# NN22_IMU_Adapter01_s00.net
KiCad netlist of a schematic drawn in EAGLE
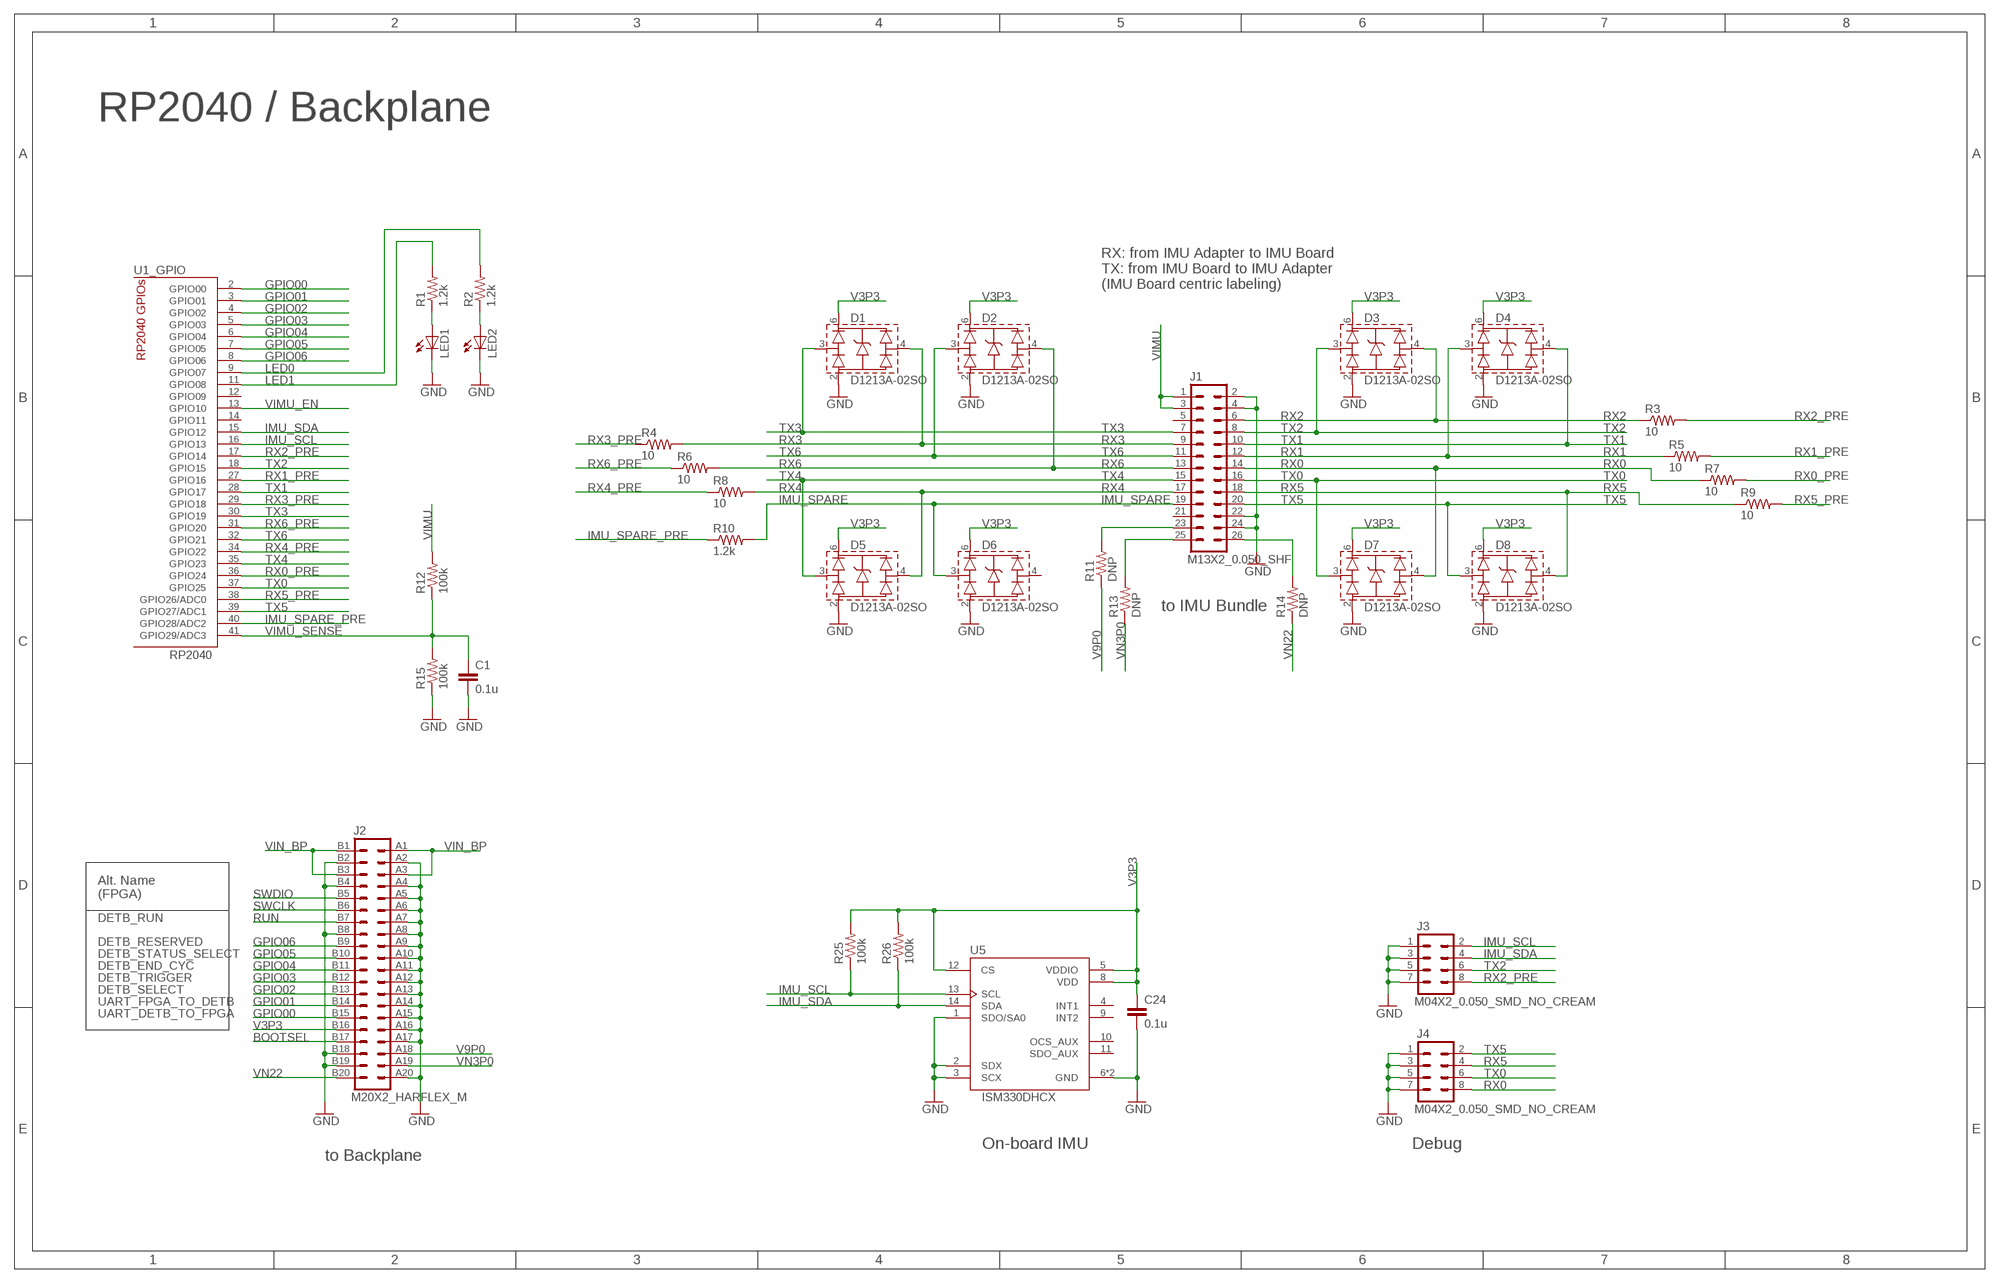
[diagram p0: schematic, sheet 1]
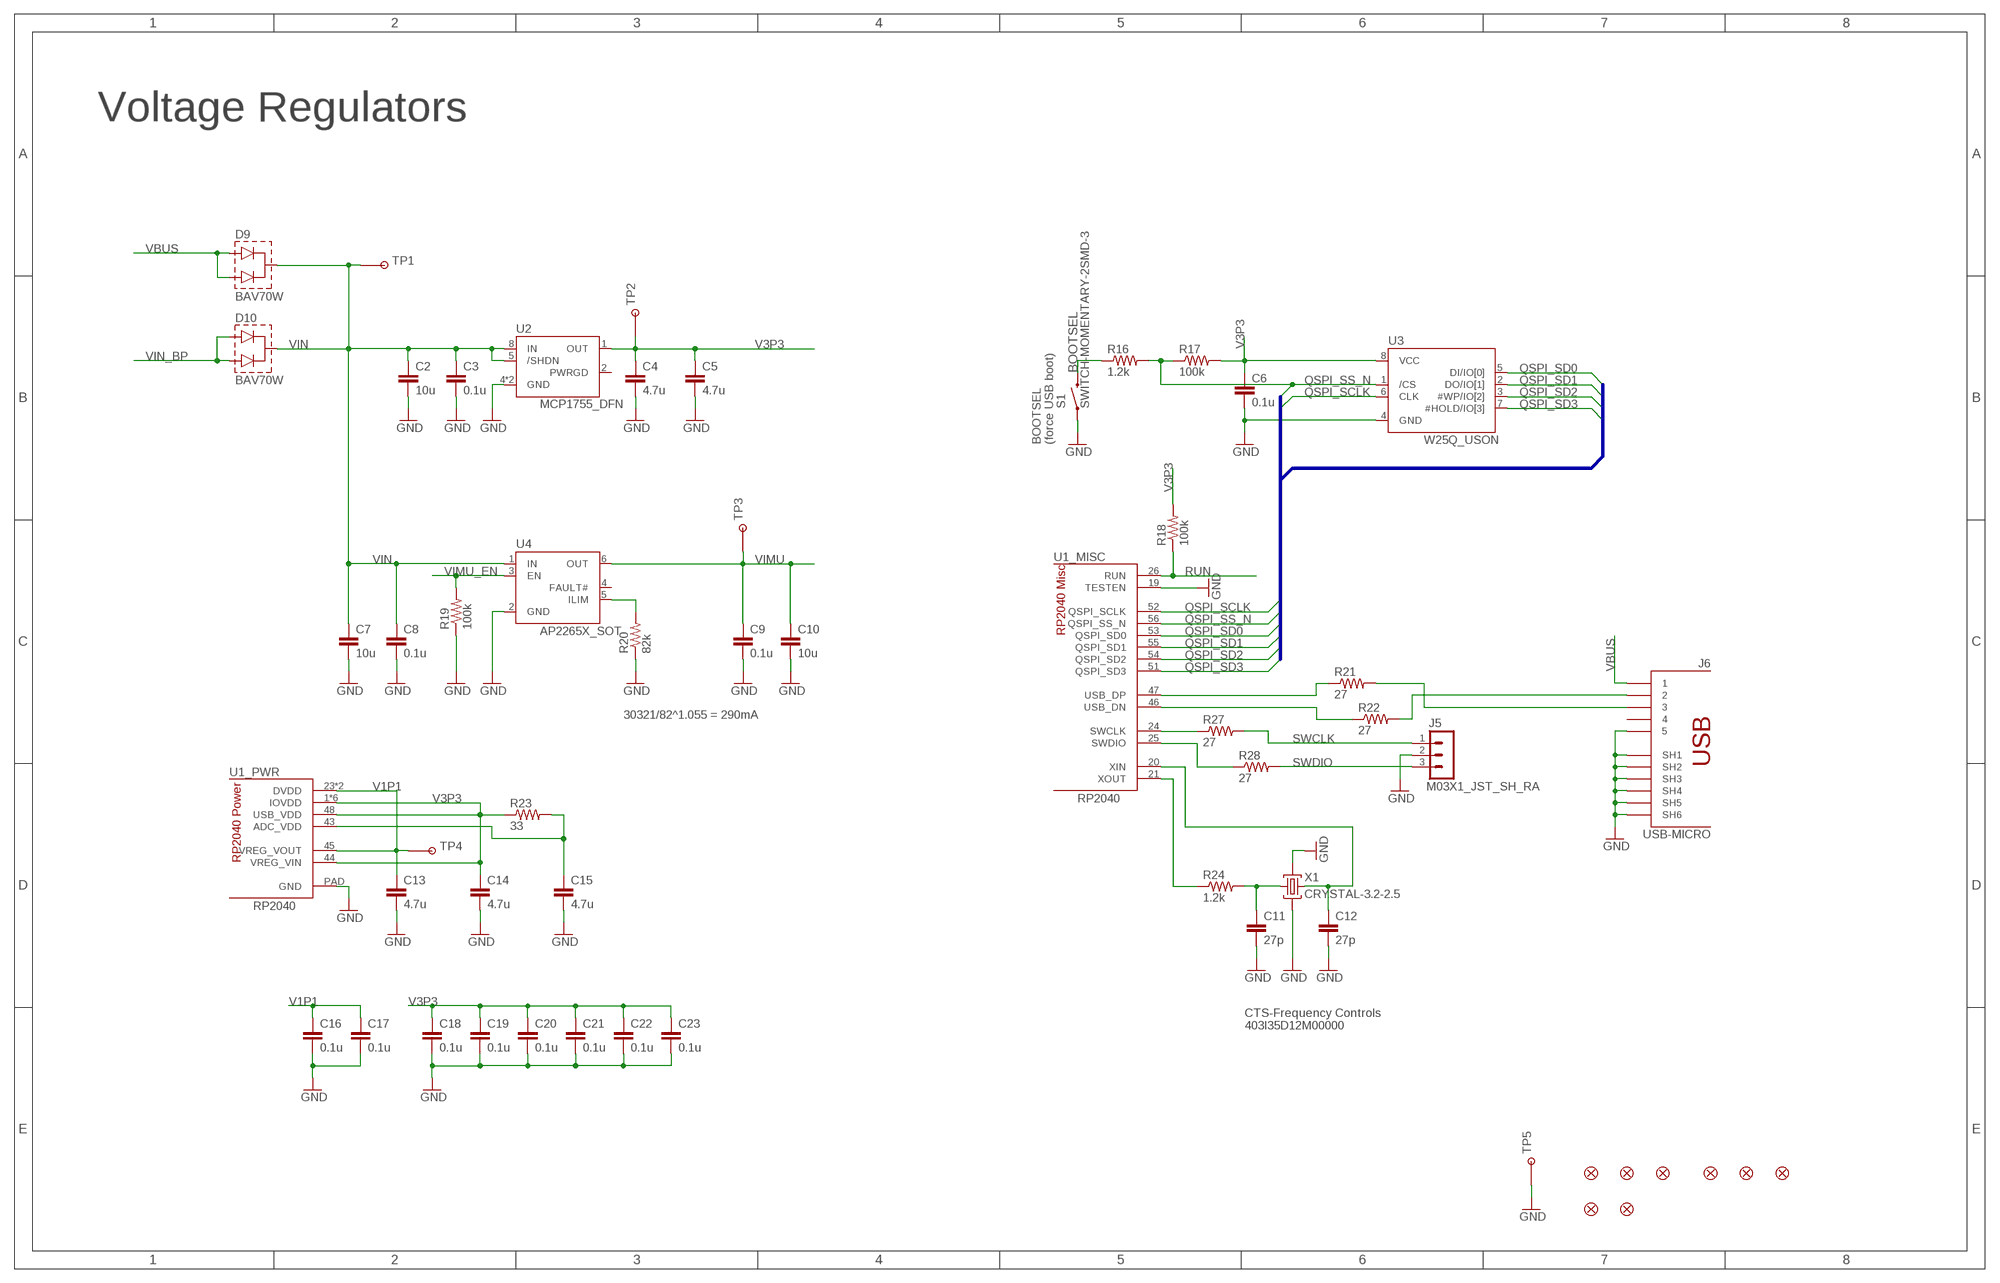
[diagram p1: schematic, sheet 2]

(export (version "E")
  (design (tool "Eeschema 10.0.6"))
  (components
    (comp (ref "C2")
      (value "10u")
      (footprint "eagle-import:0603-CAP")
      (libsource (lib "eagle-import") (part "CAP0603-CAP"))
    )
    (comp (ref "C3")
      (value "0.1u")
      (footprint "eagle-import:0402-CAP")
      (libsource (lib "eagle-import") (part "CAP0402-CAP"))
    )
    (comp (ref "C4")
      (value "4.7u")
      (footprint "eagle-import:0402-CAP")
      (libsource (lib "eagle-import") (part "CAP0402-CAP"))
    )
    (comp (ref "C5")
      (value "4.7u")
      (footprint "eagle-import:0402-CAP")
      (libsource (lib "eagle-import") (part "CAP0402-CAP"))
    )
    (comp (ref "C6")
      (value "0.1u")
      (footprint "eagle-import:0402-CAP")
      (libsource (lib "eagle-import") (part "CAP0402-CAP"))
    )
    (comp (ref "C7")
      (value "10u")
      (footprint "eagle-import:0603-CAP")
      (libsource (lib "eagle-import") (part "CAP0603-CAP"))
    )
    (comp (ref "C8")
      (value "0.1u")
      (footprint "eagle-import:0402-CAP")
      (libsource (lib "eagle-import") (part "CAP0402-CAP"))
    )
    (comp (ref "C9")
      (value "0.1u")
      (footprint "eagle-import:0402-CAP")
      (libsource (lib "eagle-import") (part "CAP0402-CAP"))
    )
    (comp (ref "C10")
      (value "10u")
      (footprint "eagle-import:0603-CAP")
      (libsource (lib "eagle-import") (part "CAP0603-CAP"))
    )
    (comp (ref "C11")
      (value "27p")
      (footprint "eagle-import:0402-CAP")
      (libsource (lib "eagle-import") (part "CAP0402-CAP"))
    )
    (comp (ref "C12")
      (value "27p")
      (footprint "eagle-import:0402-CAP")
      (libsource (lib "eagle-import") (part "CAP0402-CAP"))
    )
    (comp (ref "C13")
      (value "4.7u")
      (footprint "eagle-import:0402-CAP")
      (libsource (lib "eagle-import") (part "CAP0402-CAP"))
    )
    (comp (ref "C14")
      (value "4.7u")
      (footprint "eagle-import:0402-CAP")
      (libsource (lib "eagle-import") (part "CAP0402-CAP"))
    )
    (comp (ref "C15")
      (value "4.7u")
      (footprint "eagle-import:0402-CAP")
      (libsource (lib "eagle-import") (part "CAP0402-CAP"))
    )
    (comp (ref "C16")
      (value "0.1u")
      (footprint "eagle-import:0402-CAP")
      (libsource (lib "eagle-import") (part "CAP0402-CAP"))
    )
    (comp (ref "C17")
      (value "0.1u")
      (footprint "eagle-import:0402-CAP")
      (libsource (lib "eagle-import") (part "CAP0402-CAP"))
    )
    (comp (ref "C18")
      (value "0.1u")
      (footprint "eagle-import:0402-CAP")
      (libsource (lib "eagle-import") (part "CAP0402-CAP"))
    )
    (comp (ref "C19")
      (value "0.1u")
      (footprint "eagle-import:0402-CAP")
      (libsource (lib "eagle-import") (part "CAP0402-CAP"))
    )
    (comp (ref "C20")
      (value "0.1u")
      (footprint "eagle-import:0402-CAP")
      (libsource (lib "eagle-import") (part "CAP0402-CAP"))
    )
    (comp (ref "C21")
      (value "0.1u")
      (footprint "eagle-import:0402-CAP")
      (libsource (lib "eagle-import") (part "CAP0402-CAP"))
    )
    (comp (ref "C22")
      (value "0.1u")
      (footprint "eagle-import:0402-CAP")
      (libsource (lib "eagle-import") (part "CAP0402-CAP"))
    )
    (comp (ref "C23")
      (value "0.1u")
      (footprint "eagle-import:0402-CAP")
      (libsource (lib "eagle-import") (part "CAP0402-CAP"))
    )
    (comp (ref "D9")
      (value "BAV70W")
      (footprint "eagle-import:SOT323")
      (libsource (lib "eagle-import") (part "DIODE-COMMON_CATHODE_SOT323"))
    )
    (comp (ref "D10")
      (value "BAV70W")
      (footprint "eagle-import:SOT323")
      (libsource (lib "eagle-import") (part "DIODE-COMMON_CATHODE_SOT323"))
    )
    (comp (ref "FID1")
      (value "FIDUCIALUFIDUCIAL")
      (footprint "eagle-import:MICRO-FIDUCIAL")
      (libsource (lib "eagle-import") (part "FIDUCIALUFIDUCIAL"))
    )
    (comp (ref "FID2")
      (value "FIDUCIALUFIDUCIAL")
      (footprint "eagle-import:MICRO-FIDUCIAL")
      (libsource (lib "eagle-import") (part "FIDUCIALUFIDUCIAL"))
    )
    (comp (ref "FID3")
      (value "FIDUCIALUFIDUCIAL")
      (footprint "eagle-import:MICRO-FIDUCIAL")
      (libsource (lib "eagle-import") (part "FIDUCIALUFIDUCIAL"))
    )
    (comp (ref "FID4")
      (value "FIDUCIALUFIDUCIAL")
      (footprint "eagle-import:MICRO-FIDUCIAL")
      (libsource (lib "eagle-import") (part "FIDUCIALUFIDUCIAL"))
    )
    (comp (ref "FID5")
      (value "FIDUCIALUFIDUCIAL")
      (footprint "eagle-import:MICRO-FIDUCIAL")
      (libsource (lib "eagle-import") (part "FIDUCIALUFIDUCIAL"))
    )
    (comp (ref "FID6")
      (value "FIDUCIALUFIDUCIAL")
      (footprint "eagle-import:MICRO-FIDUCIAL")
      (libsource (lib "eagle-import") (part "FIDUCIALUFIDUCIAL"))
    )
    (comp (ref "FID7")
      (value "FIDUCIALUFIDUCIAL")
      (footprint "eagle-import:MICRO-FIDUCIAL")
      (libsource (lib "eagle-import") (part "FIDUCIALUFIDUCIAL"))
    )
    (comp (ref "FID8")
      (value "FIDUCIALUFIDUCIAL")
      (footprint "eagle-import:MICRO-FIDUCIAL")
      (libsource (lib "eagle-import") (part "FIDUCIALUFIDUCIAL"))
    )
    (comp (ref "J5")
      (value "M03X1_JST_SH_RA")
      (footprint "eagle-import:M03X1_JST_SH_SM_RA")
      (libsource (lib "eagle-import") (part "M03X1_JST_SH_RA"))
    )
    (comp (ref "J6")
      (value "USB-MICRO")
      (footprint "eagle-import:USB-MICRO")
      (libsource (lib "eagle-import") (part "USB-MICRO"))
    )
    (comp (ref "R16")
      (value "1.2k")
      (footprint "eagle-import:0402-RES")
      (libsource (lib "eagle-import") (part "RESISTOR0402-RES"))
    )
    (comp (ref "R17")
      (value "100k")
      (footprint "eagle-import:0402-RES")
      (libsource (lib "eagle-import") (part "RESISTOR0402-RES"))
    )
    (comp (ref "R18")
      (value "100k")
      (footprint "eagle-import:0402-RES")
      (libsource (lib "eagle-import") (part "RESISTOR0402-RES"))
    )
    (comp (ref "R19")
      (value "100k")
      (footprint "eagle-import:0402-RES")
      (libsource (lib "eagle-import") (part "RESISTOR0402-RES"))
    )
    (comp (ref "R20")
      (value "82k")
      (footprint "eagle-import:0402-RES")
      (libsource (lib "eagle-import") (part "RESISTOR0402-RES"))
    )
    (comp (ref "R21")
      (value "27")
      (footprint "eagle-import:0402-RES")
      (libsource (lib "eagle-import") (part "RESISTOR0402-RES"))
    )
    (comp (ref "R22")
      (value "27")
      (footprint "eagle-import:0402-RES")
      (libsource (lib "eagle-import") (part "RESISTOR0402-RES"))
    )
    (comp (ref "R23")
      (value "33")
      (footprint "eagle-import:0402-RES")
      (libsource (lib "eagle-import") (part "RESISTOR0402-RES"))
    )
    (comp (ref "R24")
      (value "1.2k")
      (footprint "eagle-import:0402-RES")
      (libsource (lib "eagle-import") (part "RESISTOR0402-RES"))
    )
    (comp (ref "R27")
      (value "27")
      (footprint "eagle-import:0402-RES")
      (libsource (lib "eagle-import") (part "RESISTOR0402-RES"))
    )
    (comp (ref "R28")
      (value "27")
      (footprint "eagle-import:0402-RES")
      (libsource (lib "eagle-import") (part "RESISTOR0402-RES"))
    )
    (comp (ref "S1")
      (value "SWITCH-MOMENTARY-2SMD-3")
      (footprint "eagle-import:TACTILE_SWITCH_SMD-3")
      (libsource (lib "eagle-import") (part "SWITCH-MOMENTARY-2SMD-3"))
    )
    (comp (ref "TP1")
      (value "TESTPOINT_ROUND")
      (footprint "eagle-import:TESTPAD_ROUND")
      (libsource (lib "eagle-import") (part "TESTPOINT_ROUND"))
    )
    (comp (ref "TP2")
      (value "TESTPOINT_ROUND")
      (footprint "eagle-import:TESTPAD_ROUND")
      (libsource (lib "eagle-import") (part "TESTPOINT_ROUND"))
    )
    (comp (ref "TP3")
      (value "TESTPOINT_ROUND")
      (footprint "eagle-import:TESTPAD_ROUND")
      (libsource (lib "eagle-import") (part "TESTPOINT_ROUND"))
    )
    (comp (ref "TP4")
      (value "TESTPOINTPADSMALL")
      (footprint "eagle-import:TESTPAD_SMALL")
      (libsource (lib "eagle-import") (part "TESTPOINTPADSMALL"))
    )
    (comp (ref "TP5")
      (value "TESTPOINT1X01")
      (footprint "eagle-import:1X01")
      (libsource (lib "eagle-import") (part "TESTPOINT1X01"))
    )
    (comp (ref "U1")
      (value "RP2040")
      (footprint "eagle-import:QFN-56_EP")
      (libsource (lib "eagle-import") (part "RP2040"))
    )
    (comp (ref "U2")
      (value "MCP1755_DFN")
      (footprint "eagle-import:DFN8_2X3MM")
      (libsource (lib "eagle-import") (part "MCP1755_DFN"))
    )
    (comp (ref "U3")
      (value "W25Q_USON")
      (footprint "eagle-import:USON8L-2X3MM")
      (libsource (lib "eagle-import") (part "W25Q_USON"))
    )
    (comp (ref "U4")
      (value "AP2265X_SOT")
      (footprint "eagle-import:SOT23-6")
      (libsource (lib "eagle-import") (part "AP2265X_SOT"))
    )
    (comp (ref "X1")
      (value "CRYSTAL-3.2-2.5")
      (footprint "eagle-import:CRYSTAL-3.2-2.5")
      (libsource (lib "eagle-import") (part "CRYSTAL-3.2-2.5"))
    )
    (comp (ref "C1")
      (value "0.1u")
      (footprint "eagle-import:0402-CAP")
      (libsource (lib "eagle-import") (part "CAP0402-CAP"))
    )
    (comp (ref "C24")
      (value "0.1u")
      (footprint "eagle-import:0402-CAP")
      (libsource (lib "eagle-import") (part "CAP0402-CAP"))
    )
    (comp (ref "D1")
      (value "D1213A-02SO")
      (footprint "eagle-import:SOT23-6")
      (libsource (lib "eagle-import") (part "D1213A-02SO"))
    )
    (comp (ref "D2")
      (value "D1213A-02SO")
      (footprint "eagle-import:SOT23-6")
      (libsource (lib "eagle-import") (part "D1213A-02SO"))
    )
    (comp (ref "D3")
      (value "D1213A-02SO")
      (footprint "eagle-import:SOT23-6")
      (libsource (lib "eagle-import") (part "D1213A-02SO"))
    )
    (comp (ref "D4")
      (value "D1213A-02SO")
      (footprint "eagle-import:SOT23-6")
      (libsource (lib "eagle-import") (part "D1213A-02SO"))
    )
    (comp (ref "D5")
      (value "D1213A-02SO")
      (footprint "eagle-import:SOT23-6")
      (libsource (lib "eagle-import") (part "D1213A-02SO"))
    )
    (comp (ref "D6")
      (value "D1213A-02SO")
      (footprint "eagle-import:SOT23-6")
      (libsource (lib "eagle-import") (part "D1213A-02SO"))
    )
    (comp (ref "D7")
      (value "D1213A-02SO")
      (footprint "eagle-import:SOT23-6")
      (libsource (lib "eagle-import") (part "D1213A-02SO"))
    )
    (comp (ref "D8")
      (value "D1213A-02SO")
      (footprint "eagle-import:SOT23-6")
      (libsource (lib "eagle-import") (part "D1213A-02SO"))
    )
    (comp (ref "J1")
      (value "M13X2_0.050_SHF")
      (footprint "eagle-import:M13X2_0.050_SHF")
      (libsource (lib "eagle-import") (part "M13X2_0.050_SHF"))
    )
    (comp (ref "J2")
      (value "M20X2_HARFLEX_M")
      (footprint "eagle-import:M20X2_HARFLEX_M")
      (libsource (lib "eagle-import") (part "M20X2_HARFLEX_M"))
    )
    (comp (ref "J3")
      (value "M04X2_0.050_SMD_NO_CREAM")
      (footprint "eagle-import:M04X2_0.050_SMD_NO_CREAM")
      (libsource (lib "eagle-import") (part "M04X2_0.050_SMD_NO_CREAM"))
    )
    (comp (ref "J4")
      (value "M04X2_0.050_SMD_NO_CREAM")
      (footprint "eagle-import:M04X2_0.050_SMD_NO_CREAM")
      (libsource (lib "eagle-import") (part "M04X2_0.050_SMD_NO_CREAM"))
    )
    (comp (ref "LED1")
      (value "LED0603")
      (footprint "eagle-import:LED-0603")
      (libsource (lib "eagle-import") (part "LED0603"))
    )
    (comp (ref "LED2")
      (value "LED0603")
      (footprint "eagle-import:LED-0603")
      (libsource (lib "eagle-import") (part "LED0603"))
    )
    (comp (ref "R1")
      (value "1.2k")
      (footprint "eagle-import:0402-RES")
      (libsource (lib "eagle-import") (part "RESISTOR0402-RES"))
    )
    (comp (ref "R2")
      (value "1.2k")
      (footprint "eagle-import:0402-RES")
      (libsource (lib "eagle-import") (part "RESISTOR0402-RES"))
    )
    (comp (ref "R3")
      (value "10")
      (footprint "eagle-import:0402-RES")
      (libsource (lib "eagle-import") (part "RESISTOR0402-RES"))
    )
    (comp (ref "R4")
      (value "10")
      (footprint "eagle-import:0402-RES")
      (libsource (lib "eagle-import") (part "RESISTOR0402-RES"))
    )
    (comp (ref "R5")
      (value "10")
      (footprint "eagle-import:0402-RES")
      (libsource (lib "eagle-import") (part "RESISTOR0402-RES"))
    )
    (comp (ref "R6")
      (value "10")
      (footprint "eagle-import:0402-RES")
      (libsource (lib "eagle-import") (part "RESISTOR0402-RES"))
    )
    (comp (ref "R7")
      (value "10")
      (footprint "eagle-import:0402-RES")
      (libsource (lib "eagle-import") (part "RESISTOR0402-RES"))
    )
    (comp (ref "R8")
      (value "10")
      (footprint "eagle-import:0402-RES")
      (libsource (lib "eagle-import") (part "RESISTOR0402-RES"))
    )
    (comp (ref "R9")
      (value "10")
      (footprint "eagle-import:0402-RES")
      (libsource (lib "eagle-import") (part "RESISTOR0402-RES"))
    )
    (comp (ref "R10")
      (value "1.2k")
      (footprint "eagle-import:0402-RES")
      (libsource (lib "eagle-import") (part "RESISTOR0402-RES"))
    )
    (comp (ref "R11")
      (value "DNP")
      (footprint "eagle-import:0603-RES")
      (libsource (lib "eagle-import") (part "RESISTOR0603-RES"))
    )
    (comp (ref "R12")
      (value "100k")
      (footprint "eagle-import:0402-RES")
      (libsource (lib "eagle-import") (part "RESISTOR0402-RES"))
    )
    (comp (ref "R13")
      (value "DNP")
      (footprint "eagle-import:0603-RES")
      (libsource (lib "eagle-import") (part "RESISTOR0603-RES"))
    )
    (comp (ref "R14")
      (value "DNP")
      (footprint "eagle-import:0603-RES")
      (libsource (lib "eagle-import") (part "RESISTOR0603-RES"))
    )
    (comp (ref "R15")
      (value "100k")
      (footprint "eagle-import:0402-RES")
      (libsource (lib "eagle-import") (part "RESISTOR0402-RES"))
    )
    (comp (ref "R25")
      (value "100k")
      (footprint "eagle-import:0402-RES")
      (libsource (lib "eagle-import") (part "RESISTOR0402-RES"))
    )
    (comp (ref "R26")
      (value "100k")
      (footprint "eagle-import:0402-RES")
      (libsource (lib "eagle-import") (part "RESISTOR0402-RES"))
    )
    (comp (ref "U5")
      (value "ISM330DHCX")
      (footprint "eagle-import:LGA14-L")
      (fields (field (name "MF") "STMicroelectronics"))
      (libsource (lib "eagle-import") (part "ISM330DHCX"))
    )
  )
  (nets
    (net (code "1") (name "BOOTSEL") (class "Default")
      (node (ref "J2") (pin "B17") (pinfunction "33_B17") (pintype "passive"))
      (node (ref "R16") (pin "1") (pinfunction "1_1") (pintype "passive"))
      (node (ref "S1") (pin "4") (pinfunction "2_4") (pintype "passive"))
    )
    (net (code "2") (name "GND") (class "Default")
      (node (ref "C1") (pin "2") (pinfunction "2_2") (pintype "passive"))
      (node (ref "C10") (pin "2") (pinfunction "2_2") (pintype "passive"))
      (node (ref "C11") (pin "2") (pinfunction "2_2") (pintype "passive"))
      (node (ref "C12") (pin "2") (pinfunction "2_2") (pintype "passive"))
      (node (ref "C13") (pin "2") (pinfunction "2_2") (pintype "passive"))
      (node (ref "C14") (pin "2") (pinfunction "2_2") (pintype "passive"))
      (node (ref "C15") (pin "2") (pinfunction "2_2") (pintype "passive"))
      (node (ref "C16") (pin "2") (pinfunction "2_2") (pintype "passive"))
      (node (ref "C17") (pin "2") (pinfunction "2_2") (pintype "passive"))
      (node (ref "C18") (pin "2") (pinfunction "2_2") (pintype "passive"))
      (node (ref "C19") (pin "2") (pinfunction "2_2") (pintype "passive"))
      (node (ref "C2") (pin "2") (pinfunction "2_2") (pintype "passive"))
      (node (ref "C20") (pin "2") (pinfunction "2_2") (pintype "passive"))
      (node (ref "C21") (pin "2") (pinfunction "2_2") (pintype "passive"))
      (node (ref "C22") (pin "2") (pinfunction "2_2") (pintype "passive"))
      (node (ref "C23") (pin "2") (pinfunction "2_2") (pintype "passive"))
      (node (ref "C24") (pin "2") (pinfunction "2_2") (pintype "passive"))
      (node (ref "C3") (pin "2") (pinfunction "2_2") (pintype "passive"))
      (node (ref "C4") (pin "2") (pinfunction "2_2") (pintype "passive"))
      (node (ref "C5") (pin "2") (pinfunction "2_2") (pintype "passive"))
      (node (ref "C6") (pin "2") (pinfunction "2_2") (pintype "passive"))
      (node (ref "C7") (pin "2") (pinfunction "2_2") (pintype "passive"))
      (node (ref "C8") (pin "2") (pinfunction "2_2") (pintype "passive"))
      (node (ref "C9") (pin "2") (pinfunction "2_2") (pintype "passive"))
      (node (ref "D1") (pin "2") (pinfunction "VN_2") (pintype "power_in"))
      (node (ref "D2") (pin "2") (pinfunction "VN_2") (pintype "power_in"))
      (node (ref "D3") (pin "2") (pinfunction "VN_2") (pintype "power_in"))
      (node (ref "D4") (pin "2") (pinfunction "VN_2") (pintype "power_in"))
      (node (ref "D5") (pin "2") (pinfunction "VN_2") (pintype "power_in"))
      (node (ref "D6") (pin "2") (pinfunction "VN_2") (pintype "power_in"))
      (node (ref "D7") (pin "2") (pinfunction "VN_2") (pintype "power_in"))
      (node (ref "D8") (pin "2") (pinfunction "VN_2") (pintype "power_in"))
      (node (ref "J1") (pin "2") (pinfunction "2_2") (pintype "passive"))
      (node (ref "J1") (pin "22") (pinfunction "22_22") (pintype "passive"))
      (node (ref "J1") (pin "24") (pinfunction "24_24") (pintype "passive"))
      (node (ref "J1") (pin "4") (pinfunction "4_4") (pintype "passive"))
      (node (ref "J2") (pin "A10") (pinfunction "20_A10") (pintype "passive"))
      (node (ref "J2") (pin "A11") (pinfunction "22_A11") (pintype "passive"))
      (node (ref "J2") (pin "A12") (pinfunction "24_A12") (pintype "passive"))
      (node (ref "J2") (pin "A13") (pinfunction "26_A13") (pintype "passive"))
      (node (ref "J2") (pin "A14") (pinfunction "28_A14") (pintype "passive"))
      (node (ref "J2") (pin "A15") (pinfunction "30_A15") (pintype "passive"))
      (node (ref "J2") (pin "A16") (pinfunction "32_A16") (pintype "passive"))
      (node (ref "J2") (pin "A17") (pinfunction "34_A17") (pintype "passive"))
      (node (ref "J2") (pin "A2") (pinfunction "4_A2") (pintype "passive"))
      (node (ref "J2") (pin "A20") (pinfunction "40_A20") (pintype "passive"))
      (node (ref "J2") (pin "A4") (pinfunction "8_A4") (pintype "passive"))
      (node (ref "J2") (pin "A5") (pinfunction "10_A5") (pintype "passive"))
      (node (ref "J2") (pin "A6") (pinfunction "12_A6") (pintype "passive"))
      (node (ref "J2") (pin "A7") (pinfunction "14_A7") (pintype "passive"))
      (node (ref "J2") (pin "A8") (pinfunction "16_A8") (pintype "passive"))
      (node (ref "J2") (pin "A9") (pinfunction "18_A9") (pintype "passive"))
      (node (ref "J2") (pin "B18") (pinfunction "35_B18") (pintype "passive"))
      (node (ref "J2") (pin "B19") (pinfunction "37_B19") (pintype "passive"))
      (node (ref "J2") (pin "B2") (pinfunction "3_B2") (pintype "passive"))
      (node (ref "J2") (pin "B4") (pinfunction "7_B4") (pintype "passive"))
      (node (ref "J2") (pin "B8") (pinfunction "15_B8") (pintype "passive"))
      (node (ref "J3") (pin "1") (pinfunction "1_1") (pintype "passive"))
      (node (ref "J3") (pin "3") (pinfunction "3_3") (pintype "passive"))
      (node (ref "J3") (pin "5") (pinfunction "5_5") (pintype "passive"))
      (node (ref "J3") (pin "7") (pinfunction "7_7") (pintype "passive"))
      (node (ref "J4") (pin "1") (pinfunction "1_1") (pintype "passive"))
      (node (ref "J4") (pin "3") (pinfunction "3_3") (pintype "passive"))
      (node (ref "J4") (pin "5") (pinfunction "5_5") (pintype "passive"))
      (node (ref "J4") (pin "7") (pinfunction "7_7") (pintype "passive"))
      (node (ref "J5") (pin "2") (pinfunction "2_2") (pintype "passive"))
      (node (ref "J6") (pin "5") (pinfunction "5_5") (pintype "bidirectional"))
      (node (ref "J6") (pin "SH1") (pinfunction "SH1_SH1") (pintype "bidirectional"))
      (node (ref "J6") (pin "SH2") (pinfunction "SH2_SH2") (pintype "bidirectional"))
      (node (ref "J6") (pin "SH3") (pinfunction "SH3_SH3") (pintype "bidirectional"))
      (node (ref "J6") (pin "SH4") (pinfunction "SH4_SH4") (pintype "bidirectional"))
      (node (ref "J6") (pin "SH5") (pinfunction "SH5_SH5") (pintype "bidirectional"))
      (node (ref "J6") (pin "SH6") (pinfunction "SH6_SH6") (pintype "bidirectional"))
      (node (ref "LED1") (pin "C") (pinfunction "C_C") (pintype "passive"))
      (node (ref "LED2") (pin "C") (pinfunction "C_C") (pintype "passive"))
      (node (ref "R15") (pin "1") (pinfunction "1_1") (pintype "passive"))
      (node (ref "R19") (pin "1") (pinfunction "1_1") (pintype "passive"))
      (node (ref "R20") (pin "1") (pinfunction "1_1") (pintype "passive"))
      (node (ref "S1") (pin "1") (pinfunction "1_1") (pintype "passive"))
      (node (ref "TP5") (pin "1") (pinfunction "P$1_1") (pintype "bidirectional"))
      (node (ref "U1") (pin "19") (pinfunction "TESTEN_19") (pintype "input"))
      (node (ref "U1") (pin "PAD") (pinfunction "GND_PAD") (pintype "power_in"))
      (node (ref "U2") (pin "4") (pinfunction "GND_4") (pintype "power_in"))
      (node (ref "U2") (pin "P") (pinfunction "GND_P") (pintype "power_in"))
      (node (ref "U3") (pin "4") (pinfunction "GND_4") (pintype "power_in"))
      (node (ref "U4") (pin "2") (pinfunction "GND_2") (pintype "power_in"))
      (node (ref "U5") (pin "1") (pinfunction "SDO/SA0_1") (pintype "bidirectional"))
      (node (ref "U5") (pin "2") (pinfunction "SDX_2") (pintype "bidirectional"))
      (node (ref "U5") (pin "3") (pinfunction "SCX_3") (pintype "bidirectional"))
      (node (ref "U5") (pin "6") (pinfunction "GND_6") (pintype "power_in"))
      (node (ref "U5") (pin "7") (pinfunction "GND_7") (pintype "power_in"))
      (node (ref "X1") (pin "2") (pinfunction "GND_2") (pintype "passive"))
      (node (ref "X1") (pin "4") (pinfunction "GND_4") (pintype "passive"))
    )
    (net (code "3") (name "GPIO00") (class "Default")
      (node (ref "J2") (pin "B15") (pinfunction "29_B15") (pintype "passive"))
      (node (ref "U1") (pin "2") (pinfunction "GPIO00_2") (pintype "bidirectional"))
    )
    (net (code "4") (name "GPIO01") (class "Default")
      (node (ref "J2") (pin "B14") (pinfunction "27_B14") (pintype "passive"))
      (node (ref "U1") (pin "3") (pinfunction "GPIO01_3") (pintype "bidirectional"))
    )
    (net (code "5") (name "GPIO02") (class "Default")
      (node (ref "J2") (pin "B13") (pinfunction "25_B13") (pintype "passive"))
      (node (ref "U1") (pin "4") (pinfunction "GPIO02_4") (pintype "bidirectional"))
    )
    (net (code "6") (name "GPIO03") (class "Default")
      (node (ref "J2") (pin "B12") (pinfunction "23_B12") (pintype "passive"))
      (node (ref "U1") (pin "5") (pinfunction "GPIO03_5") (pintype "bidirectional"))
    )
    (net (code "7") (name "GPIO04") (class "Default")
      (node (ref "J2") (pin "B11") (pinfunction "21_B11") (pintype "passive"))
      (node (ref "U1") (pin "6") (pinfunction "GPIO04_6") (pintype "bidirectional"))
    )
    (net (code "8") (name "GPIO05") (class "Default")
      (node (ref "J2") (pin "B10") (pinfunction "19_B10") (pintype "passive"))
      (node (ref "U1") (pin "7") (pinfunction "GPIO05_7") (pintype "bidirectional"))
    )
    (net (code "9") (name "GPIO06") (class "Default")
      (node (ref "J2") (pin "B9") (pinfunction "17_B9") (pintype "passive"))
      (node (ref "U1") (pin "8") (pinfunction "GPIO06_8") (pintype "bidirectional"))
    )
    (net (code "10") (name "IMU_SCL") (class "Default")
      (node (ref "J3") (pin "2") (pinfunction "2_2") (pintype "passive"))
      (node (ref "R25") (pin "1") (pinfunction "1_1") (pintype "passive"))
      (node (ref "U1") (pin "16") (pinfunction "GPIO13_16") (pintype "bidirectional"))
      (node (ref "U5") (pin "13") (pinfunction "SCL_13") (pintype "input"))
    )
    (net (code "11") (name "IMU_SDA") (class "Default")
      (node (ref "J3") (pin "4") (pinfunction "4_4") (pintype "passive"))
      (node (ref "R26") (pin "1") (pinfunction "1_1") (pintype "passive"))
      (node (ref "U1") (pin "15") (pinfunction "GPIO12_15") (pintype "bidirectional"))
      (node (ref "U5") (pin "14") (pinfunction "SDA_14") (pintype "bidirectional"))
    )
    (net (code "12") (name "IMU_SPARE") (class "Default")
      (node (ref "D6") (pin "3") (pinfunction "CH1_3") (pintype "bidirectional"))
      (node (ref "J1") (pin "19") (pinfunction "19_19") (pintype "passive"))
      (node (ref "R10") (pin "2") (pinfunction "2_2") (pintype "passive"))
    )
    (net (code "13") (name "IMU_SPARE_PRE") (class "Default")
      (node (ref "R10") (pin "1") (pinfunction "1_1") (pintype "passive"))
      (node (ref "U1") (pin "40") (pinfunction "GPIO28/ADC2_40") (pintype "bidirectional"))
    )
    (net (code "14") (name "LED0") (class "Default")
      (node (ref "R2") (pin "2") (pinfunction "2_2") (pintype "passive"))
      (node (ref "U1") (pin "9") (pinfunction "GPIO07_9") (pintype "bidirectional"))
    )
    (net (code "15") (name "LED1") (class "Default")
      (node (ref "R1") (pin "2") (pinfunction "2_2") (pintype "passive"))
      (node (ref "U1") (pin "11") (pinfunction "GPIO08_11") (pintype "bidirectional"))
    )
    (net (code "16") (name "Net-(J1-Pad23)") (class "Default")
      (node (ref "J1") (pin "23") (pinfunction "23_23") (pintype "passive"))
      (node (ref "R11") (pin "2") (pinfunction "2_2") (pintype "passive"))
    )
    (net (code "17") (name "Net-(J1-Pad25)") (class "Default")
      (node (ref "J1") (pin "25") (pinfunction "25_25") (pintype "passive"))
      (node (ref "R13") (pin "2") (pinfunction "2_2") (pintype "passive"))
    )
    (net (code "18") (name "Net-(J1-Pad26)") (class "Default")
      (node (ref "J1") (pin "26") (pinfunction "26_26") (pintype "passive"))
      (node (ref "R14") (pin "2") (pinfunction "2_2") (pintype "passive"))
    )
    (net (code "19") (name "Net-(J6-Pad2)") (class "Default")
      (node (ref "J6") (pin "2") (pinfunction "2_2") (pintype "bidirectional"))
      (node (ref "R22") (pin "2") (pinfunction "2_2") (pintype "passive"))
    )
    (net (code "20") (name "Net-(J6-Pad3)") (class "Default")
      (node (ref "J6") (pin "3") (pinfunction "3_3") (pintype "bidirectional"))
      (node (ref "R21") (pin "2") (pinfunction "2_2") (pintype "passive"))
    )
    (net (code "21") (name "Net-(LED1-PadA)") (class "Default")
      (node (ref "LED1") (pin "A") (pinfunction "A_A") (pintype "passive"))
      (node (ref "R1") (pin "1") (pinfunction "1_1") (pintype "passive"))
    )
    (net (code "22") (name "Net-(LED2-PadA)") (class "Default")
      (node (ref "LED2") (pin "A") (pinfunction "A_A") (pintype "passive"))
      (node (ref "R2") (pin "1") (pinfunction "1_1") (pintype "passive"))
    )
    (net (code "23") (name "Net-(U1B-SWCLK)") (class "Default")
      (node (ref "R27") (pin "1") (pinfunction "1_1") (pintype "passive"))
      (node (ref "U1") (pin "24") (pinfunction "SWCLK_24") (pintype "input"))
    )
    (net (code "24") (name "Net-(U1B-SWDIO)") (class "Default")
      (node (ref "R28") (pin "1") (pinfunction "1_1") (pintype "passive"))
      (node (ref "U1") (pin "25") (pinfunction "SWDIO_25") (pintype "bidirectional"))
    )
    (net (code "25") (name "Net-(U1B-USB_DN)") (class "Default")
      (node (ref "R22") (pin "1") (pinfunction "1_1") (pintype "passive"))
      (node (ref "U1") (pin "46") (pinfunction "USB_DN_46") (pintype "bidirectional"))
    )
    (net (code "26") (name "Net-(U1B-USB_DP)") (class "Default")
      (node (ref "R21") (pin "1") (pinfunction "1_1") (pintype "passive"))
      (node (ref "U1") (pin "47") (pinfunction "USB_DP_47") (pintype "bidirectional"))
    )
    (net (code "27") (name "Net-(U1B-XIN)") (class "Default")
      (node (ref "C12") (pin "1") (pinfunction "1_1") (pintype "passive"))
      (node (ref "U1") (pin "20") (pinfunction "XIN_20") (pintype "bidirectional"))
      (node (ref "X1") (pin "3") (pinfunction "C2_3") (pintype "passive"))
    )
    (net (code "28") (name "Net-(U1B-XOUT)") (class "Default")
      (node (ref "R24") (pin "1") (pinfunction "1_1") (pintype "passive"))
      (node (ref "U1") (pin "21") (pinfunction "XOUT_21") (pintype "bidirectional"))
    )
    (net (code "29") (name "Net-(U1C-ADC_VDD)") (class "Default")
      (node (ref "C15") (pin "1") (pinfunction "1_1") (pintype "passive"))
      (node (ref "R23") (pin "2") (pinfunction "2_2") (pintype "passive"))
      (node (ref "U1") (pin "43") (pinfunction "ADC_VDD_43") (pintype "power_in"))
    )
    (net (code "30") (name "Net-(U4-ILIM)") (class "Default")
      (node (ref "R20") (pin "2") (pinfunction "2_2") (pintype "passive"))
      (node (ref "U4") (pin "5") (pinfunction "ILIM_5") (pintype "bidirectional"))
    )
    (net (code "31") (name "Net-(X1-C1)") (class "Default")
      (node (ref "C11") (pin "1") (pinfunction "1_1") (pintype "passive"))
      (node (ref "R24") (pin "2") (pinfunction "2_2") (pintype "passive"))
      (node (ref "X1") (pin "1") (pinfunction "C1_1") (pintype "passive"))
    )
    (net (code "32") (name "QSPI_SCLK") (class "Default")
      (node (ref "U1") (pin "52") (pinfunction "QSPI_SCLK_52") (pintype "output"))
      (node (ref "U3") (pin "6") (pinfunction "CLK_6") (pintype "input"))
    )
    (net (code "33") (name "QSPI_SD0") (class "Default")
      (node (ref "U1") (pin "53") (pinfunction "QSPI_SD0_53") (pintype "bidirectional"))
      (node (ref "U3") (pin "5") (pinfunction "DI/IO[0]_5") (pintype "bidirectional"))
    )
    (net (code "34") (name "QSPI_SD1") (class "Default")
      (node (ref "U1") (pin "55") (pinfunction "QSPI_SD1_55") (pintype "bidirectional"))
      (node (ref "U3") (pin "2") (pinfunction "DO/IO[1]_2") (pintype "bidirectional"))
    )
    (net (code "35") (name "QSPI_SD2") (class "Default")
      (node (ref "U1") (pin "54") (pinfunction "QSPI_SD2_54") (pintype "bidirectional"))
      (node (ref "U3") (pin "3") (pinfunction "#WP/IO[2]_3") (pintype "bidirectional"))
    )
    (net (code "36") (name "QSPI_SD3") (class "Default")
      (node (ref "U1") (pin "51") (pinfunction "QSPI_SD3_51") (pintype "bidirectional"))
      (node (ref "U3") (pin "7") (pinfunction "#HOLD/IO[3]_7") (pintype "bidirectional"))
    )
    (net (code "37") (name "QSPI_SS_N") (class "Default")
      (node (ref "R16") (pin "2") (pinfunction "2_2") (pintype "passive"))
      (node (ref "R17") (pin "1") (pinfunction "1_1") (pintype "passive"))
      (node (ref "U1") (pin "56") (pinfunction "QSPI_SS_N_56") (pintype "output"))
      (node (ref "U3") (pin "1") (pinfunction "/CS_1") (pintype "input"))
    )
    (net (code "38") (name "RUN") (class "Default")
      (node (ref "J2") (pin "B7") (pinfunction "13_B7") (pintype "passive"))
      (node (ref "R18") (pin "1") (pinfunction "1_1") (pintype "passive"))
      (node (ref "U1") (pin "26") (pinfunction "RUN_26") (pintype "input"))
    )
    (net (code "39") (name "RX0") (class "Default")
      (node (ref "D7") (pin "4") (pinfunction "CH2_4") (pintype "bidirectional"))
      (node (ref "J1") (pin "14") (pinfunction "14_14") (pintype "passive"))
      (node (ref "J4") (pin "8") (pinfunction "8_8") (pintype "passive"))
      (node (ref "R7") (pin "1") (pinfunction "1_1") (pintype "passive"))
    )
    (net (code "40") (name "RX0_PRE") (class "Default")
      (node (ref "R7") (pin "2") (pinfunction "2_2") (pintype "passive"))
      (node (ref "U1") (pin "36") (pinfunction "GPIO24_36") (pintype "bidirectional"))
    )
    (net (code "41") (name "RX1") (class "Default")
      (node (ref "D4") (pin "3") (pinfunction "CH1_3") (pintype "bidirectional"))
      (node (ref "J1") (pin "12") (pinfunction "12_12") (pintype "passive"))
      (node (ref "R5") (pin "1") (pinfunction "1_1") (pintype "passive"))
    )
    (net (code "42") (name "RX1_PRE") (class "Default")
      (node (ref "R5") (pin "2") (pinfunction "2_2") (pintype "passive"))
      (node (ref "U1") (pin "27") (pinfunction "GPIO16_27") (pintype "bidirectional"))
    )
    (net (code "43") (name "RX2") (class "Default")
      (node (ref "D3") (pin "4") (pinfunction "CH2_4") (pintype "bidirectional"))
      (node (ref "J1") (pin "6") (pinfunction "6_6") (pintype "passive"))
      (node (ref "R3") (pin "1") (pinfunction "1_1") (pintype "passive"))
    )
    (net (code "44") (name "RX2_PRE") (class "Default")
      (node (ref "J3") (pin "8") (pinfunction "8_8") (pintype "passive"))
      (node (ref "R3") (pin "2") (pinfunction "2_2") (pintype "passive"))
      (node (ref "U1") (pin "17") (pinfunction "GPIO14_17") (pintype "bidirectional"))
    )
    (net (code "45") (name "RX3") (class "Default")
      (node (ref "D1") (pin "4") (pinfunction "CH2_4") (pintype "bidirectional"))
      (node (ref "J1") (pin "9") (pinfunction "9_9") (pintype "passive"))
      (node (ref "R4") (pin "2") (pinfunction "2_2") (pintype "passive"))
    )
    (net (code "46") (name "RX3_PRE") (class "Default")
      (node (ref "R4") (pin "1") (pinfunction "1_1") (pintype "passive"))
      (node (ref "U1") (pin "29") (pinfunction "GPIO18_29") (pintype "bidirectional"))
    )
    (net (code "47") (name "RX4") (class "Default")
      (node (ref "D5") (pin "4") (pinfunction "CH2_4") (pintype "bidirectional"))
      (node (ref "J1") (pin "17") (pinfunction "17_17") (pintype "passive"))
      (node (ref "R8") (pin "2") (pinfunction "2_2") (pintype "passive"))
    )
    (net (code "48") (name "RX4_PRE") (class "Default")
      (node (ref "R8") (pin "1") (pinfunction "1_1") (pintype "passive"))
      (node (ref "U1") (pin "34") (pinfunction "GPIO22_34") (pintype "bidirectional"))
    )
    (net (code "49") (name "RX5") (class "Default")
      (node (ref "D8") (pin "4") (pinfunction "CH2_4") (pintype "bidirectional"))
      (node (ref "J1") (pin "18") (pinfunction "18_18") (pintype "passive"))
      (node (ref "J4") (pin "4") (pinfunction "4_4") (pintype "passive"))
      (node (ref "R9") (pin "1") (pinfunction "1_1") (pintype "passive"))
    )
    (net (code "50") (name "RX5_PRE") (class "Default")
      (node (ref "R9") (pin "2") (pinfunction "2_2") (pintype "passive"))
      (node (ref "U1") (pin "38") (pinfunction "GPIO26/ADC0_38") (pintype "bidirectional"))
    )
    (net (code "51") (name "RX6") (class "Default")
      (node (ref "D2") (pin "4") (pinfunction "CH2_4") (pintype "bidirectional"))
      (node (ref "J1") (pin "13") (pinfunction "13_13") (pintype "passive"))
      (node (ref "R6") (pin "2") (pinfunction "2_2") (pintype "passive"))
    )
    (net (code "52") (name "RX6_PRE") (class "Default")
      (node (ref "R6") (pin "1") (pinfunction "1_1") (pintype "passive"))
      (node (ref "U1") (pin "31") (pinfunction "GPIO20_31") (pintype "bidirectional"))
    )
    (net (code "53") (name "SWCLK") (class "Default")
      (node (ref "J2") (pin "B6") (pinfunction "11_B6") (pintype "passive"))
      (node (ref "J5") (pin "1") (pinfunction "1_1") (pintype "passive"))
      (node (ref "R27") (pin "2") (pinfunction "2_2") (pintype "passive"))
    )
    (net (code "54") (name "SWDIO") (class "Default")
      (node (ref "J2") (pin "B5") (pinfunction "9_B5") (pintype "passive"))
      (node (ref "J5") (pin "3") (pinfunction "3_3") (pintype "passive"))
      (node (ref "R28") (pin "2") (pinfunction "2_2") (pintype "passive"))
    )
    (net (code "55") (name "TX0") (class "Default")
      (node (ref "D7") (pin "3") (pinfunction "CH1_3") (pintype "bidirectional"))
      (node (ref "J1") (pin "16") (pinfunction "16_16") (pintype "passive"))
      (node (ref "J4") (pin "6") (pinfunction "6_6") (pintype "passive"))
      (node (ref "U1") (pin "37") (pinfunction "GPIO25_37") (pintype "bidirectional"))
    )
    (net (code "56") (name "TX1") (class "Default")
      (node (ref "D4") (pin "4") (pinfunction "CH2_4") (pintype "bidirectional"))
      (node (ref "J1") (pin "10") (pinfunction "10_10") (pintype "passive"))
      (node (ref "U1") (pin "28") (pinfunction "GPIO17_28") (pintype "bidirectional"))
    )
    (net (code "57") (name "TX2") (class "Default")
      (node (ref "D3") (pin "3") (pinfunction "CH1_3") (pintype "bidirectional"))
      (node (ref "J1") (pin "8") (pinfunction "8_8") (pintype "passive"))
      (node (ref "J3") (pin "6") (pinfunction "6_6") (pintype "passive"))
      (node (ref "U1") (pin "18") (pinfunction "GPIO15_18") (pintype "bidirectional"))
    )
    (net (code "58") (name "TX3") (class "Default")
      (node (ref "D1") (pin "3") (pinfunction "CH1_3") (pintype "bidirectional"))
      (node (ref "J1") (pin "7") (pinfunction "7_7") (pintype "passive"))
      (node (ref "U1") (pin "30") (pinfunction "GPIO19_30") (pintype "bidirectional"))
    )
    (net (code "59") (name "TX4") (class "Default")
      (node (ref "D5") (pin "3") (pinfunction "CH1_3") (pintype "bidirectional"))
      (node (ref "J1") (pin "15") (pinfunction "15_15") (pintype "passive"))
      (node (ref "U1") (pin "35") (pinfunction "GPIO23_35") (pintype "bidirectional"))
    )
    (net (code "60") (name "TX5") (class "Default")
      (node (ref "D8") (pin "3") (pinfunction "CH1_3") (pintype "bidirectional"))
      (node (ref "J1") (pin "20") (pinfunction "20_20") (pintype "passive"))
      (node (ref "J4") (pin "2") (pinfunction "2_2") (pintype "passive"))
      (node (ref "U1") (pin "39") (pinfunction "GPIO27/ADC1_39") (pintype "bidirectional"))
    )
    (net (code "61") (name "TX6") (class "Default")
      (node (ref "D2") (pin "3") (pinfunction "CH1_3") (pintype "bidirectional"))
      (node (ref "J1") (pin "11") (pinfunction "11_11") (pintype "passive"))
      (node (ref "U1") (pin "32") (pinfunction "GPIO21_32") (pintype "bidirectional"))
    )
    (net (code "62") (name "V1P1") (class "Default")
      (node (ref "C13") (pin "1") (pinfunction "1_1") (pintype "passive"))
      (node (ref "C16") (pin "1") (pinfunction "1_1") (pintype "passive"))
      (node (ref "C17") (pin "1") (pinfunction "1_1") (pintype "passive"))
      (node (ref "TP4") (pin "P$1") (pinfunction "P$1_P$1") (pintype "bidirectional"))
      (node (ref "U1") (pin "23") (pinfunction "DVDD_23") (pintype "power_in"))
      (node (ref "U1") (pin "45") (pinfunction "VREG_VOUT_45") (pintype "power_in"))
      (node (ref "U1") (pin "50") (pinfunction "DVDD_50") (pintype "power_in"))
    )
    (net (code "63") (name "V3P3") (class "Default")
      (node (ref "C14") (pin "1") (pinfunction "1_1") (pintype "passive"))
      (node (ref "C18") (pin "1") (pinfunction "1_1") (pintype "passive"))
      (node (ref "C19") (pin "1") (pinfunction "1_1") (pintype "passive"))
      (node (ref "C20") (pin "1") (pinfunction "1_1") (pintype "passive"))
      (node (ref "C21") (pin "1") (pinfunction "1_1") (pintype "passive"))
      (node (ref "C22") (pin "1") (pinfunction "1_1") (pintype "passive"))
      (node (ref "C23") (pin "1") (pinfunction "1_1") (pintype "passive"))
      (node (ref "C24") (pin "1") (pinfunction "1_1") (pintype "passive"))
      (node (ref "C4") (pin "1") (pinfunction "1_1") (pintype "passive"))
      (node (ref "C5") (pin "1") (pinfunction "1_1") (pintype "passive"))
      (node (ref "C6") (pin "1") (pinfunction "1_1") (pintype "passive"))
      (node (ref "D1") (pin "6") (pinfunction "VP_6") (pintype "power_in"))
      (node (ref "D2") (pin "6") (pinfunction "VP_6") (pintype "power_in"))
      (node (ref "D3") (pin "6") (pinfunction "VP_6") (pintype "power_in"))
      (node (ref "D4") (pin "6") (pinfunction "VP_6") (pintype "power_in"))
      (node (ref "D5") (pin "6") (pinfunction "VP_6") (pintype "power_in"))
      (node (ref "D6") (pin "6") (pinfunction "VP_6") (pintype "power_in"))
      (node (ref "D7") (pin "6") (pinfunction "VP_6") (pintype "power_in"))
      (node (ref "D8") (pin "6") (pinfunction "VP_6") (pintype "power_in"))
      (node (ref "J2") (pin "B16") (pinfunction "31_B16") (pintype "passive"))
      (node (ref "R17") (pin "2") (pinfunction "2_2") (pintype "passive"))
      (node (ref "R18") (pin "2") (pinfunction "2_2") (pintype "passive"))
      (node (ref "R23") (pin "1") (pinfunction "1_1") (pintype "passive"))
      (node (ref "R25") (pin "2") (pinfunction "2_2") (pintype "passive"))
      (node (ref "R26") (pin "2") (pinfunction "2_2") (pintype "passive"))
      (node (ref "TP2") (pin "P$1") (pinfunction "P$1_P$1") (pintype "bidirectional"))
      (node (ref "U1") (pin "1") (pinfunction "IOVDD_1") (pintype "power_in"))
      (node (ref "U1") (pin "10") (pinfunction "IOVDD_10") (pintype "power_in"))
      (node (ref "U1") (pin "22") (pinfunction "IOVDD_22") (pintype "power_in"))
      (node (ref "U1") (pin "33") (pinfunction "IOVDD_33") (pintype "power_in"))
      (node (ref "U1") (pin "42") (pinfunction "IOVDD_42") (pintype "power_in"))
      (node (ref "U1") (pin "44") (pinfunction "VREG_VIN_44") (pintype "power_in"))
      (node (ref "U1") (pin "48") (pinfunction "USB_VDD_48") (pintype "power_in"))
      (node (ref "U1") (pin "49") (pinfunction "IOVDD_49") (pintype "power_in"))
      (node (ref "U2") (pin "1") (pinfunction "OUT_1") (pintype "power_in"))
      (node (ref "U3") (pin "8") (pinfunction "VCC_8") (pintype "power_in"))
      (node (ref "U5") (pin "12") (pinfunction "CS_12") (pintype "input"))
      (node (ref "U5") (pin "5") (pinfunction "VDDIO_5") (pintype "power_in"))
      (node (ref "U5") (pin "8") (pinfunction "VDD_8") (pintype "power_in"))
    )
    (net (code "64") (name "V9P0") (class "Default")
      (node (ref "J2") (pin "A18") (pinfunction "36_A18") (pintype "passive"))
      (node (ref "R11") (pin "1") (pinfunction "1_1") (pintype "passive"))
    )
    (net (code "65") (name "VBUS") (class "Default")
      (node (ref "D9") (pin "1") (pinfunction "A1_1") (pintype "bidirectional"))
      (node (ref "D9") (pin "2") (pinfunction "A2_2") (pintype "bidirectional"))
      (node (ref "J6") (pin "1") (pinfunction "1_1") (pintype "bidirectional"))
    )
    (net (code "66") (name "VIMU") (class "Default")
      (node (ref "C10") (pin "1") (pinfunction "1_1") (pintype "passive"))
      (node (ref "C9") (pin "1") (pinfunction "1_1") (pintype "passive"))
      (node (ref "J1") (pin "1") (pinfunction "1_1") (pintype "passive"))
      (node (ref "J1") (pin "3") (pinfunction "3_3") (pintype "passive"))
      (node (ref "R12") (pin "2") (pinfunction "2_2") (pintype "passive"))
      (node (ref "TP3") (pin "P$1") (pinfunction "P$1_P$1") (pintype "bidirectional"))
      (node (ref "U4") (pin "6") (pinfunction "OUT_6") (pintype "power_in"))
    )
    (net (code "67") (name "VIMU_EN") (class "Default")
      (node (ref "R19") (pin "2") (pinfunction "2_2") (pintype "passive"))
      (node (ref "U1") (pin "13") (pinfunction "GPIO10_13") (pintype "bidirectional"))
      (node (ref "U4") (pin "3") (pinfunction "EN_3") (pintype "input"))
    )
    (net (code "68") (name "VIMU_SENSE") (class "Default")
      (node (ref "C1") (pin "1") (pinfunction "1_1") (pintype "passive"))
      (node (ref "R12") (pin "1") (pinfunction "1_1") (pintype "passive"))
      (node (ref "R15") (pin "2") (pinfunction "2_2") (pintype "passive"))
      (node (ref "U1") (pin "41") (pinfunction "GPIO29/ADC3_41") (pintype "bidirectional"))
    )
    (net (code "69") (name "VIN") (class "Default")
      (node (ref "C2") (pin "1") (pinfunction "1_1") (pintype "passive"))
      (node (ref "C3") (pin "1") (pinfunction "1_1") (pintype "passive"))
      (node (ref "C7") (pin "1") (pinfunction "1_1") (pintype "passive"))
      (node (ref "C8") (pin "1") (pinfunction "1_1") (pintype "passive"))
      (node (ref "D10") (pin "3") (pinfunction "C_3") (pintype "bidirectional"))
      (node (ref "D9") (pin "3") (pinfunction "C_3") (pintype "bidirectional"))
      (node (ref "TP1") (pin "P$1") (pinfunction "P$1_P$1") (pintype "bidirectional"))
      (node (ref "U2") (pin "5") (pinfunction "/SHDN_5") (pintype "input"))
      (node (ref "U2") (pin "8") (pinfunction "IN_8") (pintype "power_in"))
      (node (ref "U4") (pin "1") (pinfunction "IN_1") (pintype "power_in"))
    )
    (net (code "70") (name "VIN_BP") (class "Default")
      (node (ref "D10") (pin "1") (pinfunction "A1_1") (pintype "bidirectional"))
      (node (ref "D10") (pin "2") (pinfunction "A2_2") (pintype "bidirectional"))
      (node (ref "J2") (pin "A1") (pinfunction "2_A1") (pintype "passive"))
      (node (ref "J2") (pin "A3") (pinfunction "6_A3") (pintype "passive"))
      (node (ref "J2") (pin "B1") (pinfunction "1_B1") (pintype "passive"))
      (node (ref "J2") (pin "B3") (pinfunction "5_B3") (pintype "passive"))
    )
    (net (code "71") (name "VN3P0") (class "Default")
      (node (ref "J2") (pin "A19") (pinfunction "38_A19") (pintype "passive"))
      (node (ref "R13") (pin "1") (pinfunction "1_1") (pintype "passive"))
    )
    (net (code "72") (name "VN22") (class "Default")
      (node (ref "J2") (pin "B20") (pinfunction "39_B20") (pintype "passive"))
      (node (ref "R14") (pin "1") (pinfunction "1_1") (pintype "passive"))
    )
    (net (code "73") (name "unconnected-(D6-CH2-Pad4)") (class "Default")
      (node (ref "D6") (pin "4") (pinfunction "CH2_4") (pintype "bidirectional"))
    )
    (net (code "74") (name "unconnected-(J1-Pad5)") (class "Default")
      (node (ref "J1") (pin "5") (pinfunction "5_5") (pintype "passive"))
    )
    (net (code "75") (name "unconnected-(J1-Pad21)") (class "Default")
      (node (ref "J1") (pin "21") (pinfunction "21_21") (pintype "passive"))
    )
    (net (code "76") (name "unconnected-(J6-Pad4)") (class "Default")
      (node (ref "J6") (pin "4") (pinfunction "4_4") (pintype "bidirectional"))
    )
    (net (code "77") (name "unconnected-(U1A-GPIO09-Pad12)") (class "Default")
      (node (ref "U1") (pin "12") (pinfunction "GPIO09_12") (pintype "bidirectional"))
    )
    (net (code "78") (name "unconnected-(U1A-GPIO11-Pad14)") (class "Default")
      (node (ref "U1") (pin "14") (pinfunction "GPIO11_14") (pintype "bidirectional"))
    )
    (net (code "79") (name "unconnected-(U2-PWRGD-Pad2)") (class "Default")
      (node (ref "U2") (pin "2") (pinfunction "PWRGD_2") (pintype "output"))
    )
    (net (code "80") (name "unconnected-(U4-FAULT#-Pad4)") (class "Default")
      (node (ref "U4") (pin "4") (pinfunction "FAULT#_4") (pintype "open_collector"))
    )
    (net (code "81") (name "unconnected-(U5-INT1-Pad4)") (class "Default")
      (node (ref "U5") (pin "4") (pinfunction "INT1_4") (pintype "output"))
    )
    (net (code "82") (name "unconnected-(U5-INT2-Pad9)") (class "Default")
      (node (ref "U5") (pin "9") (pinfunction "INT2_9") (pintype "output"))
    )
    (net (code "83") (name "unconnected-(U5-OCS_AUX-Pad10)") (class "Default")
      (node (ref "U5") (pin "10") (pinfunction "OCS_AUX_10") (pintype "input"))
    )
    (net (code "84") (name "unconnected-(U5-SDO_AUX-Pad11)") (class "Default")
      (node (ref "U5") (pin "11") (pinfunction "SDO_AUX_11") (pintype "bidirectional"))
    )
  )
)
